# IOs.net
KiCad netlist of a schematic drawn in Altium Designer
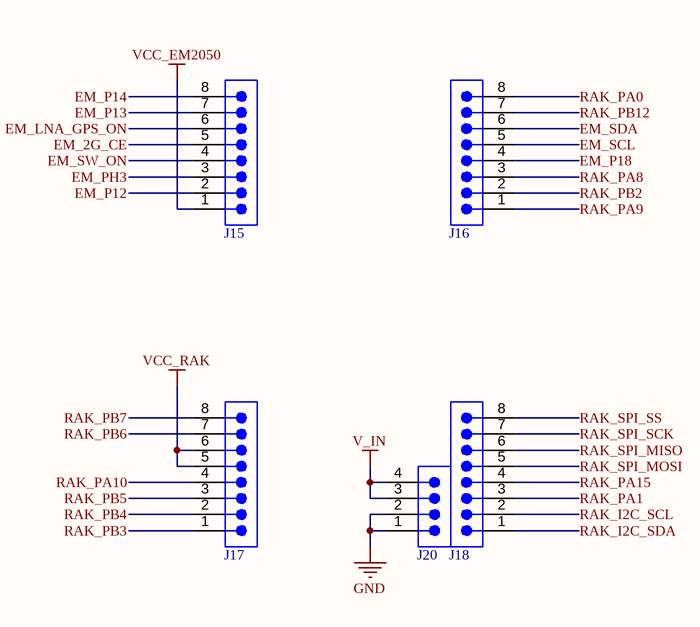
[diagram p0: IOs.SchDoc]

(export (version "E")
  (design (tool "Eeschema 10.0.6"))
  (components
    (comp (ref "J15")
      (value "61300811121")
      (footprint "61300811121")
      (libsource (lib "Altium Content Vault") (part "Header_Male_1R_08P"))
    )
    (comp (ref "J16")
      (value "61300811121")
      (footprint "61300811121")
      (libsource (lib "Altium Content Vault") (part "Header_Male_1R_08P"))
    )
    (comp (ref "J17")
      (value "61300811121")
      (footprint "61300811121")
      (libsource (lib "Altium Content Vault") (part "Header_Male_1R_08P"))
    )
    (comp (ref "J18")
      (value "61300811121")
      (footprint "61300811121")
      (libsource (lib "Altium Content Vault") (part "Header_Male_1R_08P"))
    )
    (comp (ref "J20")
      (value "61300411121")
      (footprint "61300411121")
      (libsource (lib "Altium Content Vault") (part "Header_Male_1R_04P"))
    )
  )
  (nets
    (net (code "1") (name "/EM_2G_CE") (class "Default")
      (node (ref "J15") (pin "5") (pinfunction "5_5") (pintype "passive"))
    )
    (net (code "2") (name "/EM_LNA_GPS_ON") (class "Default")
      (node (ref "J15") (pin "6") (pinfunction "6_6") (pintype "passive"))
    )
    (net (code "3") (name "/EM_P12") (class "Default")
      (node (ref "J15") (pin "2") (pinfunction "2_2") (pintype "passive"))
    )
    (net (code "4") (name "/EM_P13") (class "Default")
      (node (ref "J15") (pin "7") (pinfunction "7_7") (pintype "passive"))
    )
    (net (code "5") (name "/EM_P14") (class "Default")
      (node (ref "J15") (pin "8") (pinfunction "8_8") (pintype "passive"))
    )
    (net (code "6") (name "/EM_P18") (class "Default")
      (node (ref "J16") (pin "4") (pinfunction "4_4") (pintype "passive"))
    )
    (net (code "7") (name "/EM_PH3") (class "Default")
      (node (ref "J15") (pin "3") (pinfunction "3_3") (pintype "passive"))
    )
    (net (code "8") (name "/EM_SCL") (class "Default")
      (node (ref "J16") (pin "5") (pinfunction "5_5") (pintype "passive"))
    )
    (net (code "9") (name "/EM_SDA") (class "Default")
      (node (ref "J16") (pin "6") (pinfunction "6_6") (pintype "passive"))
    )
    (net (code "10") (name "/EM_SW_ON") (class "Default")
      (node (ref "J15") (pin "4") (pinfunction "4_4") (pintype "passive"))
    )
    (net (code "11") (name "/RAK_I2C_SCL") (class "Default")
      (node (ref "J18") (pin "2") (pinfunction "2_2") (pintype "passive"))
    )
    (net (code "12") (name "/RAK_I2C_SDA") (class "Default")
      (node (ref "J18") (pin "1") (pinfunction "1_1") (pintype "passive"))
    )
    (net (code "13") (name "/RAK_PA0") (class "Default")
      (node (ref "J16") (pin "8") (pinfunction "8_8") (pintype "passive"))
    )
    (net (code "14") (name "/RAK_PA1") (class "Default")
      (node (ref "J18") (pin "3") (pinfunction "3_3") (pintype "passive"))
    )
    (net (code "15") (name "/RAK_PA8") (class "Default")
      (node (ref "J16") (pin "3") (pinfunction "3_3") (pintype "passive"))
    )
    (net (code "16") (name "/RAK_PA9") (class "Default")
      (node (ref "J16") (pin "1") (pinfunction "1_1") (pintype "passive"))
    )
    (net (code "17") (name "/RAK_PA10") (class "Default")
      (node (ref "J17") (pin "4") (pinfunction "4_4") (pintype "passive"))
    )
    (net (code "18") (name "/RAK_PA15") (class "Default")
      (node (ref "J18") (pin "4") (pinfunction "4_4") (pintype "passive"))
    )
    (net (code "19") (name "/RAK_PB2") (class "Default")
      (node (ref "J16") (pin "2") (pinfunction "2_2") (pintype "passive"))
    )
    (net (code "20") (name "/RAK_PB3") (class "Default")
      (node (ref "J17") (pin "1") (pinfunction "1_1") (pintype "passive"))
    )
    (net (code "21") (name "/RAK_PB4") (class "Default")
      (node (ref "J17") (pin "2") (pinfunction "2_2") (pintype "passive"))
    )
    (net (code "22") (name "/RAK_PB5") (class "Default")
      (node (ref "J17") (pin "3") (pinfunction "3_3") (pintype "passive"))
    )
    (net (code "23") (name "/RAK_PB6") (class "Default")
      (node (ref "J17") (pin "7") (pinfunction "7_7") (pintype "passive"))
    )
    (net (code "24") (name "/RAK_PB7") (class "Default")
      (node (ref "J17") (pin "8") (pinfunction "8_8") (pintype "passive"))
    )
    (net (code "25") (name "/RAK_PB12") (class "Default")
      (node (ref "J16") (pin "7") (pinfunction "7_7") (pintype "passive"))
    )
    (net (code "26") (name "/RAK_SPI_MISO") (class "Default")
      (node (ref "J18") (pin "6") (pinfunction "6_6") (pintype "passive"))
    )
    (net (code "27") (name "/RAK_SPI_MOSI") (class "Default")
      (node (ref "J18") (pin "5") (pinfunction "5_5") (pintype "passive"))
    )
    (net (code "28") (name "/RAK_SPI_SCK") (class "Default")
      (node (ref "J18") (pin "7") (pinfunction "7_7") (pintype "passive"))
    )
    (net (code "29") (name "/RAK_SPI_SS") (class "Default")
      (node (ref "J18") (pin "8") (pinfunction "8_8") (pintype "passive"))
    )
    (net (code "30") (name "GND") (class "Default")
      (node (ref "J20") (pin "1") (pinfunction "1_1") (pintype "passive"))
      (node (ref "J20") (pin "2") (pinfunction "2_2") (pintype "passive"))
    )
    (net (code "31") (name "VCC_EM2050") (class "Default")
      (node (ref "J15") (pin "1") (pinfunction "1_1") (pintype "passive"))
    )
    (net (code "32") (name "VCC_RAK") (class "Default")
      (node (ref "J17") (pin "5") (pinfunction "5_5") (pintype "passive"))
      (node (ref "J17") (pin "6") (pinfunction "6_6") (pintype "passive"))
    )
    (net (code "33") (name "V_IN") (class "Default")
      (node (ref "J20") (pin "3") (pinfunction "3_3") (pintype "passive"))
      (node (ref "J20") (pin "4") (pinfunction "4_4") (pintype "passive"))
    )
  )
)
